# dankboard-xs-ortho.net
KiCad netlist of a schematic drawn in Altium Designer
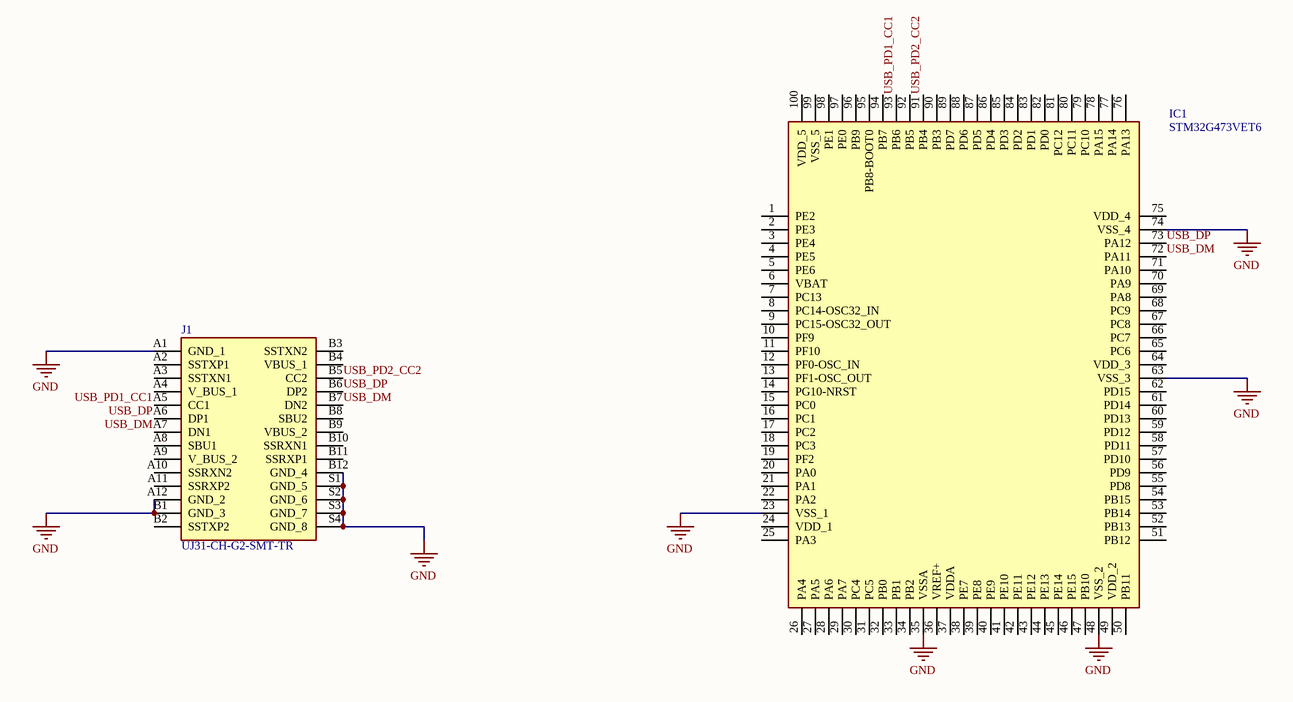
[diagram p0: dankboard-xs-ortho.SchDoc]

(export (version "E")
  (design (tool "Eeschema 10.0.6"))
  (components
    (comp (ref "IC1")
      (value "STM32G473VET6")
      (footprint "SamacSys:QFP50P1600X1600X160-100N")
      (description "Integrated Circuit")
      (fields (field (name "MOUSER PART NUMBER") "511-STM32G473VET6"))
      (libsource (lib "*") (part "STM32G473VET6"))
    )
    (comp (ref "J1")
      (value "UJ31-CH-G2-SMT-TR")
      (footprint "SamacSys:UJ31CHG2SMTTR")
      (description "Connector")
      (fields (field (name "MOUSER PART NUMBER") "490-UJ31-CH-G2SMT-TR"))
      (libsource (lib "SamacSys") (part "UJ31-CH-G2-SMT-TR"))
    )
  )
  (nets
    (net (code "1") (name "/USB_DM") (class "Default")
      (node (ref "IC1") (pin "72") (pinfunction "PA11_72") (pintype "passive"))
      (node (ref "J1") (pin "A7") (pinfunction "DN1_A7") (pintype "passive"))
      (node (ref "J1") (pin "B7") (pinfunction "DN2_B7") (pintype "passive"))
    )
    (net (code "2") (name "/USB_DP") (class "Default")
      (node (ref "IC1") (pin "73") (pinfunction "PA12_73") (pintype "passive"))
      (node (ref "J1") (pin "A6") (pinfunction "DP1_A6") (pintype "passive"))
      (node (ref "J1") (pin "B6") (pinfunction "DP2_B6") (pintype "passive"))
    )
    (net (code "3") (name "/USB_PD1_CC1") (class "Default")
      (node (ref "IC1") (pin "93") (pinfunction "PB6_93") (pintype "passive"))
      (node (ref "J1") (pin "A5") (pinfunction "CC1_A5") (pintype "passive"))
    )
    (net (code "4") (name "/USB_PD2_CC2") (class "Default")
      (node (ref "IC1") (pin "91") (pinfunction "PB4_91") (pintype "passive"))
      (node (ref "J1") (pin "B5") (pinfunction "CC2_B5") (pintype "passive"))
    )
    (net (code "5") (name "GND") (class "Default")
      (node (ref "IC1") (pin "23") (pinfunction "VSS_1_23") (pintype "passive"))
      (node (ref "IC1") (pin "35") (pinfunction "VSSA_35") (pintype "passive"))
      (node (ref "IC1") (pin "48") (pinfunction "VSS_2_48") (pintype "passive"))
      (node (ref "IC1") (pin "63") (pinfunction "VSS_3_63") (pintype "passive"))
      (node (ref "IC1") (pin "74") (pinfunction "VSS_4_74") (pintype "passive"))
      (node (ref "J1") (pin "A1") (pinfunction "GND_1_A1") (pintype "passive"))
      (node (ref "J1") (pin "A12") (pinfunction "GND_2_A12") (pintype "passive"))
      (node (ref "J1") (pin "B1") (pinfunction "GND_3_B1") (pintype "passive"))
      (node (ref "J1") (pin "B12") (pinfunction "GND_4_B12") (pintype "passive"))
      (node (ref "J1") (pin "S1") (pinfunction "GND_5_S1") (pintype "passive"))
      (node (ref "J1") (pin "S2") (pinfunction "GND_6_S2") (pintype "passive"))
      (node (ref "J1") (pin "S3") (pinfunction "GND_7_S3") (pintype "passive"))
      (node (ref "J1") (pin "S4") (pinfunction "GND_8_S4") (pintype "passive"))
    )
    (net (code "6") (name "unconnected-(IC1-PA0-Pad20)") (class "Default")
      (node (ref "IC1") (pin "20") (pinfunction "PA0_20") (pintype "passive"))
    )
    (net (code "7") (name "unconnected-(IC1-PA1-Pad21)") (class "Default")
      (node (ref "IC1") (pin "21") (pinfunction "PA1_21") (pintype "passive"))
    )
    (net (code "8") (name "unconnected-(IC1-PA2-Pad22)") (class "Default")
      (node (ref "IC1") (pin "22") (pinfunction "PA2_22") (pintype "passive"))
    )
    (net (code "9") (name "unconnected-(IC1-PA3-Pad25)") (class "Default")
      (node (ref "IC1") (pin "25") (pinfunction "PA3_25") (pintype "passive"))
    )
    (net (code "10") (name "unconnected-(IC1-PA4-Pad26)") (class "Default")
      (node (ref "IC1") (pin "26") (pinfunction "PA4_26") (pintype "passive"))
    )
    (net (code "11") (name "unconnected-(IC1-PA5-Pad27)") (class "Default")
      (node (ref "IC1") (pin "27") (pinfunction "PA5_27") (pintype "passive"))
    )
    (net (code "12") (name "unconnected-(IC1-PA6-Pad28)") (class "Default")
      (node (ref "IC1") (pin "28") (pinfunction "PA6_28") (pintype "passive"))
    )
    (net (code "13") (name "unconnected-(IC1-PA7-Pad29)") (class "Default")
      (node (ref "IC1") (pin "29") (pinfunction "PA7_29") (pintype "passive"))
    )
    (net (code "14") (name "unconnected-(IC1-PA8-Pad69)") (class "Default")
      (node (ref "IC1") (pin "69") (pinfunction "PA8_69") (pintype "passive"))
    )
    (net (code "15") (name "unconnected-(IC1-PA9-Pad70)") (class "Default")
      (node (ref "IC1") (pin "70") (pinfunction "PA9_70") (pintype "passive"))
    )
    (net (code "16") (name "unconnected-(IC1-PA10-Pad71)") (class "Default")
      (node (ref "IC1") (pin "71") (pinfunction "PA10_71") (pintype "passive"))
    )
    (net (code "17") (name "unconnected-(IC1-PA13-Pad76)") (class "Default")
      (node (ref "IC1") (pin "76") (pinfunction "PA13_76") (pintype "passive"))
    )
    (net (code "18") (name "unconnected-(IC1-PA14-Pad77)") (class "Default")
      (node (ref "IC1") (pin "77") (pinfunction "PA14_77") (pintype "passive"))
    )
    (net (code "19") (name "unconnected-(IC1-PA15-Pad78)") (class "Default")
      (node (ref "IC1") (pin "78") (pinfunction "PA15_78") (pintype "passive"))
    )
    (net (code "20") (name "unconnected-(IC1-PB0-Pad32)") (class "Default")
      (node (ref "IC1") (pin "32") (pinfunction "PB0_32") (pintype "passive"))
    )
    (net (code "21") (name "unconnected-(IC1-PB1-Pad33)") (class "Default")
      (node (ref "IC1") (pin "33") (pinfunction "PB1_33") (pintype "passive"))
    )
    (net (code "22") (name "unconnected-(IC1-PB2-Pad34)") (class "Default")
      (node (ref "IC1") (pin "34") (pinfunction "PB2_34") (pintype "passive"))
    )
    (net (code "23") (name "unconnected-(IC1-PB3-Pad90)") (class "Default")
      (node (ref "IC1") (pin "90") (pinfunction "PB3_90") (pintype "passive"))
    )
    (net (code "24") (name "unconnected-(IC1-PB5-Pad92)") (class "Default")
      (node (ref "IC1") (pin "92") (pinfunction "PB5_92") (pintype "passive"))
    )
    (net (code "25") (name "unconnected-(IC1-PB7-Pad94)") (class "Default")
      (node (ref "IC1") (pin "94") (pinfunction "PB7_94") (pintype "passive"))
    )
    (net (code "26") (name "unconnected-(IC1-PB8-BOOT0-Pad95)") (class "Default")
      (node (ref "IC1") (pin "95") (pinfunction "PB8-BOOT0_95") (pintype "passive"))
    )
    (net (code "27") (name "unconnected-(IC1-PB9-Pad96)") (class "Default")
      (node (ref "IC1") (pin "96") (pinfunction "PB9_96") (pintype "passive"))
    )
    (net (code "28") (name "unconnected-(IC1-PB10-Pad47)") (class "Default")
      (node (ref "IC1") (pin "47") (pinfunction "PB10_47") (pintype "passive"))
    )
    (net (code "29") (name "unconnected-(IC1-PB11-Pad50)") (class "Default")
      (node (ref "IC1") (pin "50") (pinfunction "PB11_50") (pintype "passive"))
    )
    (net (code "30") (name "unconnected-(IC1-PB12-Pad51)") (class "Default")
      (node (ref "IC1") (pin "51") (pinfunction "PB12_51") (pintype "passive"))
    )
    (net (code "31") (name "unconnected-(IC1-PB13-Pad52)") (class "Default")
      (node (ref "IC1") (pin "52") (pinfunction "PB13_52") (pintype "passive"))
    )
    (net (code "32") (name "unconnected-(IC1-PB14-Pad53)") (class "Default")
      (node (ref "IC1") (pin "53") (pinfunction "PB14_53") (pintype "passive"))
    )
    (net (code "33") (name "unconnected-(IC1-PB15-Pad54)") (class "Default")
      (node (ref "IC1") (pin "54") (pinfunction "PB15_54") (pintype "passive"))
    )
    (net (code "34") (name "unconnected-(IC1-PC0-Pad15)") (class "Default")
      (node (ref "IC1") (pin "15") (pinfunction "PC0_15") (pintype "passive"))
    )
    (net (code "35") (name "unconnected-(IC1-PC1-Pad16)") (class "Default")
      (node (ref "IC1") (pin "16") (pinfunction "PC1_16") (pintype "passive"))
    )
    (net (code "36") (name "unconnected-(IC1-PC2-Pad17)") (class "Default")
      (node (ref "IC1") (pin "17") (pinfunction "PC2_17") (pintype "passive"))
    )
    (net (code "37") (name "unconnected-(IC1-PC3-Pad18)") (class "Default")
      (node (ref "IC1") (pin "18") (pinfunction "PC3_18") (pintype "passive"))
    )
    (net (code "38") (name "unconnected-(IC1-PC4-Pad30)") (class "Default")
      (node (ref "IC1") (pin "30") (pinfunction "PC4_30") (pintype "passive"))
    )
    (net (code "39") (name "unconnected-(IC1-PC5-Pad31)") (class "Default")
      (node (ref "IC1") (pin "31") (pinfunction "PC5_31") (pintype "passive"))
    )
    (net (code "40") (name "unconnected-(IC1-PC6-Pad65)") (class "Default")
      (node (ref "IC1") (pin "65") (pinfunction "PC6_65") (pintype "passive"))
    )
    (net (code "41") (name "unconnected-(IC1-PC7-Pad66)") (class "Default")
      (node (ref "IC1") (pin "66") (pinfunction "PC7_66") (pintype "passive"))
    )
    (net (code "42") (name "unconnected-(IC1-PC8-Pad67)") (class "Default")
      (node (ref "IC1") (pin "67") (pinfunction "PC8_67") (pintype "passive"))
    )
    (net (code "43") (name "unconnected-(IC1-PC9-Pad68)") (class "Default")
      (node (ref "IC1") (pin "68") (pinfunction "PC9_68") (pintype "passive"))
    )
    (net (code "44") (name "unconnected-(IC1-PC10-Pad79)") (class "Default")
      (node (ref "IC1") (pin "79") (pinfunction "PC10_79") (pintype "passive"))
    )
    (net (code "45") (name "unconnected-(IC1-PC11-Pad80)") (class "Default")
      (node (ref "IC1") (pin "80") (pinfunction "PC11_80") (pintype "passive"))
    )
    (net (code "46") (name "unconnected-(IC1-PC12-Pad81)") (class "Default")
      (node (ref "IC1") (pin "81") (pinfunction "PC12_81") (pintype "passive"))
    )
    (net (code "47") (name "unconnected-(IC1-PC13-Pad7)") (class "Default")
      (node (ref "IC1") (pin "7") (pinfunction "PC13_7") (pintype "passive"))
    )
    (net (code "48") (name "unconnected-(IC1-PC14-OSC32_IN-Pad8)") (class "Default")
      (node (ref "IC1") (pin "8") (pinfunction "PC14-OSC32_IN_8") (pintype "passive"))
    )
    (net (code "49") (name "unconnected-(IC1-PC15-OSC32_OUT-Pad9)") (class "Default")
      (node (ref "IC1") (pin "9") (pinfunction "PC15-OSC32_OUT_9") (pintype "passive"))
    )
    (net (code "50") (name "unconnected-(IC1-PD0-Pad82)") (class "Default")
      (node (ref "IC1") (pin "82") (pinfunction "PD0_82") (pintype "passive"))
    )
    (net (code "51") (name "unconnected-(IC1-PD1-Pad83)") (class "Default")
      (node (ref "IC1") (pin "83") (pinfunction "PD1_83") (pintype "passive"))
    )
    (net (code "52") (name "unconnected-(IC1-PD2-Pad84)") (class "Default")
      (node (ref "IC1") (pin "84") (pinfunction "PD2_84") (pintype "passive"))
    )
    (net (code "53") (name "unconnected-(IC1-PD3-Pad85)") (class "Default")
      (node (ref "IC1") (pin "85") (pinfunction "PD3_85") (pintype "passive"))
    )
    (net (code "54") (name "unconnected-(IC1-PD4-Pad86)") (class "Default")
      (node (ref "IC1") (pin "86") (pinfunction "PD4_86") (pintype "passive"))
    )
    (net (code "55") (name "unconnected-(IC1-PD5-Pad87)") (class "Default")
      (node (ref "IC1") (pin "87") (pinfunction "PD5_87") (pintype "passive"))
    )
    (net (code "56") (name "unconnected-(IC1-PD6-Pad88)") (class "Default")
      (node (ref "IC1") (pin "88") (pinfunction "PD6_88") (pintype "passive"))
    )
    (net (code "57") (name "unconnected-(IC1-PD7-Pad89)") (class "Default")
      (node (ref "IC1") (pin "89") (pinfunction "PD7_89") (pintype "passive"))
    )
    (net (code "58") (name "unconnected-(IC1-PD8-Pad55)") (class "Default")
      (node (ref "IC1") (pin "55") (pinfunction "PD8_55") (pintype "passive"))
    )
    (net (code "59") (name "unconnected-(IC1-PD9-Pad56)") (class "Default")
      (node (ref "IC1") (pin "56") (pinfunction "PD9_56") (pintype "passive"))
    )
    (net (code "60") (name "unconnected-(IC1-PD10-Pad57)") (class "Default")
      (node (ref "IC1") (pin "57") (pinfunction "PD10_57") (pintype "passive"))
    )
    (net (code "61") (name "unconnected-(IC1-PD11-Pad58)") (class "Default")
      (node (ref "IC1") (pin "58") (pinfunction "PD11_58") (pintype "passive"))
    )
    (net (code "62") (name "unconnected-(IC1-PD12-Pad59)") (class "Default")
      (node (ref "IC1") (pin "59") (pinfunction "PD12_59") (pintype "passive"))
    )
    (net (code "63") (name "unconnected-(IC1-PD13-Pad60)") (class "Default")
      (node (ref "IC1") (pin "60") (pinfunction "PD13_60") (pintype "passive"))
    )
    (net (code "64") (name "unconnected-(IC1-PD14-Pad61)") (class "Default")
      (node (ref "IC1") (pin "61") (pinfunction "PD14_61") (pintype "passive"))
    )
    (net (code "65") (name "unconnected-(IC1-PD15-Pad62)") (class "Default")
      (node (ref "IC1") (pin "62") (pinfunction "PD15_62") (pintype "passive"))
    )
    (net (code "66") (name "unconnected-(IC1-PE0-Pad97)") (class "Default")
      (node (ref "IC1") (pin "97") (pinfunction "PE0_97") (pintype "passive"))
    )
    (net (code "67") (name "unconnected-(IC1-PE1-Pad98)") (class "Default")
      (node (ref "IC1") (pin "98") (pinfunction "PE1_98") (pintype "passive"))
    )
    (net (code "68") (name "unconnected-(IC1-PE2-Pad1)") (class "Default")
      (node (ref "IC1") (pin "1") (pinfunction "PE2_1") (pintype "passive"))
    )
    (net (code "69") (name "unconnected-(IC1-PE3-Pad2)") (class "Default")
      (node (ref "IC1") (pin "2") (pinfunction "PE3_2") (pintype "passive"))
    )
    (net (code "70") (name "unconnected-(IC1-PE4-Pad3)") (class "Default")
      (node (ref "IC1") (pin "3") (pinfunction "PE4_3") (pintype "passive"))
    )
    (net (code "71") (name "unconnected-(IC1-PE5-Pad4)") (class "Default")
      (node (ref "IC1") (pin "4") (pinfunction "PE5_4") (pintype "passive"))
    )
    (net (code "72") (name "unconnected-(IC1-PE6-Pad5)") (class "Default")
      (node (ref "IC1") (pin "5") (pinfunction "PE6_5") (pintype "passive"))
    )
    (net (code "73") (name "unconnected-(IC1-PE7-Pad38)") (class "Default")
      (node (ref "IC1") (pin "38") (pinfunction "PE7_38") (pintype "passive"))
    )
    (net (code "74") (name "unconnected-(IC1-PE8-Pad39)") (class "Default")
      (node (ref "IC1") (pin "39") (pinfunction "PE8_39") (pintype "passive"))
    )
    (net (code "75") (name "unconnected-(IC1-PE9-Pad40)") (class "Default")
      (node (ref "IC1") (pin "40") (pinfunction "PE9_40") (pintype "passive"))
    )
    (net (code "76") (name "unconnected-(IC1-PE10-Pad41)") (class "Default")
      (node (ref "IC1") (pin "41") (pinfunction "PE10_41") (pintype "passive"))
    )
    (net (code "77") (name "unconnected-(IC1-PE11-Pad42)") (class "Default")
      (node (ref "IC1") (pin "42") (pinfunction "PE11_42") (pintype "passive"))
    )
    (net (code "78") (name "unconnected-(IC1-PE12-Pad43)") (class "Default")
      (node (ref "IC1") (pin "43") (pinfunction "PE12_43") (pintype "passive"))
    )
    (net (code "79") (name "unconnected-(IC1-PE13-Pad44)") (class "Default")
      (node (ref "IC1") (pin "44") (pinfunction "PE13_44") (pintype "passive"))
    )
    (net (code "80") (name "unconnected-(IC1-PE14-Pad45)") (class "Default")
      (node (ref "IC1") (pin "45") (pinfunction "PE14_45") (pintype "passive"))
    )
    (net (code "81") (name "unconnected-(IC1-PE15-Pad46)") (class "Default")
      (node (ref "IC1") (pin "46") (pinfunction "PE15_46") (pintype "passive"))
    )
    (net (code "82") (name "unconnected-(IC1-PF0-OSC_IN-Pad12)") (class "Default")
      (node (ref "IC1") (pin "12") (pinfunction "PF0-OSC_IN_12") (pintype "passive"))
    )
    (net (code "83") (name "unconnected-(IC1-PF1-OSC_OUT-Pad13)") (class "Default")
      (node (ref "IC1") (pin "13") (pinfunction "PF1-OSC_OUT_13") (pintype "passive"))
    )
    (net (code "84") (name "unconnected-(IC1-PF2-Pad19)") (class "Default")
      (node (ref "IC1") (pin "19") (pinfunction "PF2_19") (pintype "passive"))
    )
    (net (code "85") (name "unconnected-(IC1-PF9-Pad10)") (class "Default")
      (node (ref "IC1") (pin "10") (pinfunction "PF9_10") (pintype "passive"))
    )
    (net (code "86") (name "unconnected-(IC1-PF10-Pad11)") (class "Default")
      (node (ref "IC1") (pin "11") (pinfunction "PF10_11") (pintype "passive"))
    )
    (net (code "87") (name "unconnected-(IC1-PG10-NRST-Pad14)") (class "Default")
      (node (ref "IC1") (pin "14") (pinfunction "PG10-NRST_14") (pintype "passive"))
    )
    (net (code "88") (name "unconnected-(IC1-VBAT-Pad6)") (class "Default")
      (node (ref "IC1") (pin "6") (pinfunction "VBAT_6") (pintype "passive"))
    )
    (net (code "89") (name "unconnected-(IC1-VDDA-Pad37)") (class "Default")
      (node (ref "IC1") (pin "37") (pinfunction "VDDA_37") (pintype "passive"))
    )
    (net (code "90") (name "unconnected-(IC1-VDD_1-Pad24)") (class "Default")
      (node (ref "IC1") (pin "24") (pinfunction "VDD_1_24") (pintype "passive"))
    )
    (net (code "91") (name "unconnected-(IC1-VDD_2-Pad49)") (class "Default")
      (node (ref "IC1") (pin "49") (pinfunction "VDD_2_49") (pintype "passive"))
    )
    (net (code "92") (name "unconnected-(IC1-VDD_3-Pad64)") (class "Default")
      (node (ref "IC1") (pin "64") (pinfunction "VDD_3_64") (pintype "passive"))
    )
    (net (code "93") (name "unconnected-(IC1-VDD_4-Pad75)") (class "Default")
      (node (ref "IC1") (pin "75") (pinfunction "VDD_4_75") (pintype "passive"))
    )
    (net (code "94") (name "unconnected-(IC1-VDD_5-Pad100)") (class "Default")
      (node (ref "IC1") (pin "100") (pinfunction "VDD_5_100") (pintype "passive"))
    )
    (net (code "95") (name "unconnected-(IC1-VREF+-Pad36)") (class "Default")
      (node (ref "IC1") (pin "36") (pinfunction "VREF+_36") (pintype "passive"))
    )
    (net (code "96") (name "unconnected-(IC1-VSS_5-Pad99)") (class "Default")
      (node (ref "IC1") (pin "99") (pinfunction "VSS_5_99") (pintype "passive"))
    )
    (net (code "97") (name "unconnected-(J1-SBU1-PadA8)") (class "Default")
      (node (ref "J1") (pin "A8") (pinfunction "SBU1_A8") (pintype "passive"))
    )
    (net (code "98") (name "unconnected-(J1-SBU2-PadB8)") (class "Default")
      (node (ref "J1") (pin "B8") (pinfunction "SBU2_B8") (pintype "passive"))
    )
    (net (code "99") (name "unconnected-(J1-SSRXN1-PadB10)") (class "Default")
      (node (ref "J1") (pin "B10") (pinfunction "SSRXN1_B10") (pintype "passive"))
    )
    (net (code "100") (name "unconnected-(J1-SSRXN2-PadA10)") (class "Default")
      (node (ref "J1") (pin "A10") (pinfunction "SSRXN2_A10") (pintype "passive"))
    )
    (net (code "101") (name "unconnected-(J1-SSRXP1-PadB11)") (class "Default")
      (node (ref "J1") (pin "B11") (pinfunction "SSRXP1_B11") (pintype "passive"))
    )
    (net (code "102") (name "unconnected-(J1-SSRXP2-PadA11)") (class "Default")
      (node (ref "J1") (pin "A11") (pinfunction "SSRXP2_A11") (pintype "passive"))
    )
    (net (code "103") (name "unconnected-(J1-SSTXN1-PadA3)") (class "Default")
      (node (ref "J1") (pin "A3") (pinfunction "SSTXN1_A3") (pintype "passive"))
    )
    (net (code "104") (name "unconnected-(J1-SSTXN2-PadB3)") (class "Default")
      (node (ref "J1") (pin "B3") (pinfunction "SSTXN2_B3") (pintype "passive"))
    )
    (net (code "105") (name "unconnected-(J1-SSTXP1-PadA2)") (class "Default")
      (node (ref "J1") (pin "A2") (pinfunction "SSTXP1_A2") (pintype "passive"))
    )
    (net (code "106") (name "unconnected-(J1-SSTXP2-PadB2)") (class "Default")
      (node (ref "J1") (pin "B2") (pinfunction "SSTXP2_B2") (pintype "passive"))
    )
    (net (code "107") (name "unconnected-(J1-VBUS_1-PadB4)") (class "Default")
      (node (ref "J1") (pin "B4") (pinfunction "VBUS_1_B4") (pintype "passive"))
    )
    (net (code "108") (name "unconnected-(J1-VBUS_2-PadB9)") (class "Default")
      (node (ref "J1") (pin "B9") (pinfunction "VBUS_2_B9") (pintype "passive"))
    )
    (net (code "109") (name "unconnected-(J1-V_BUS_1-PadA4)") (class "Default")
      (node (ref "J1") (pin "A4") (pinfunction "V_BUS_1_A4") (pintype "passive"))
    )
    (net (code "110") (name "unconnected-(J1-V_BUS_2-PadA9)") (class "Default")
      (node (ref "J1") (pin "A9") (pinfunction "V_BUS_2_A9") (pintype "passive"))
    )
  )
)
